# XMICRO-LPA_V1_0.net
KiCad netlist of a schematic drawn in EAGLE
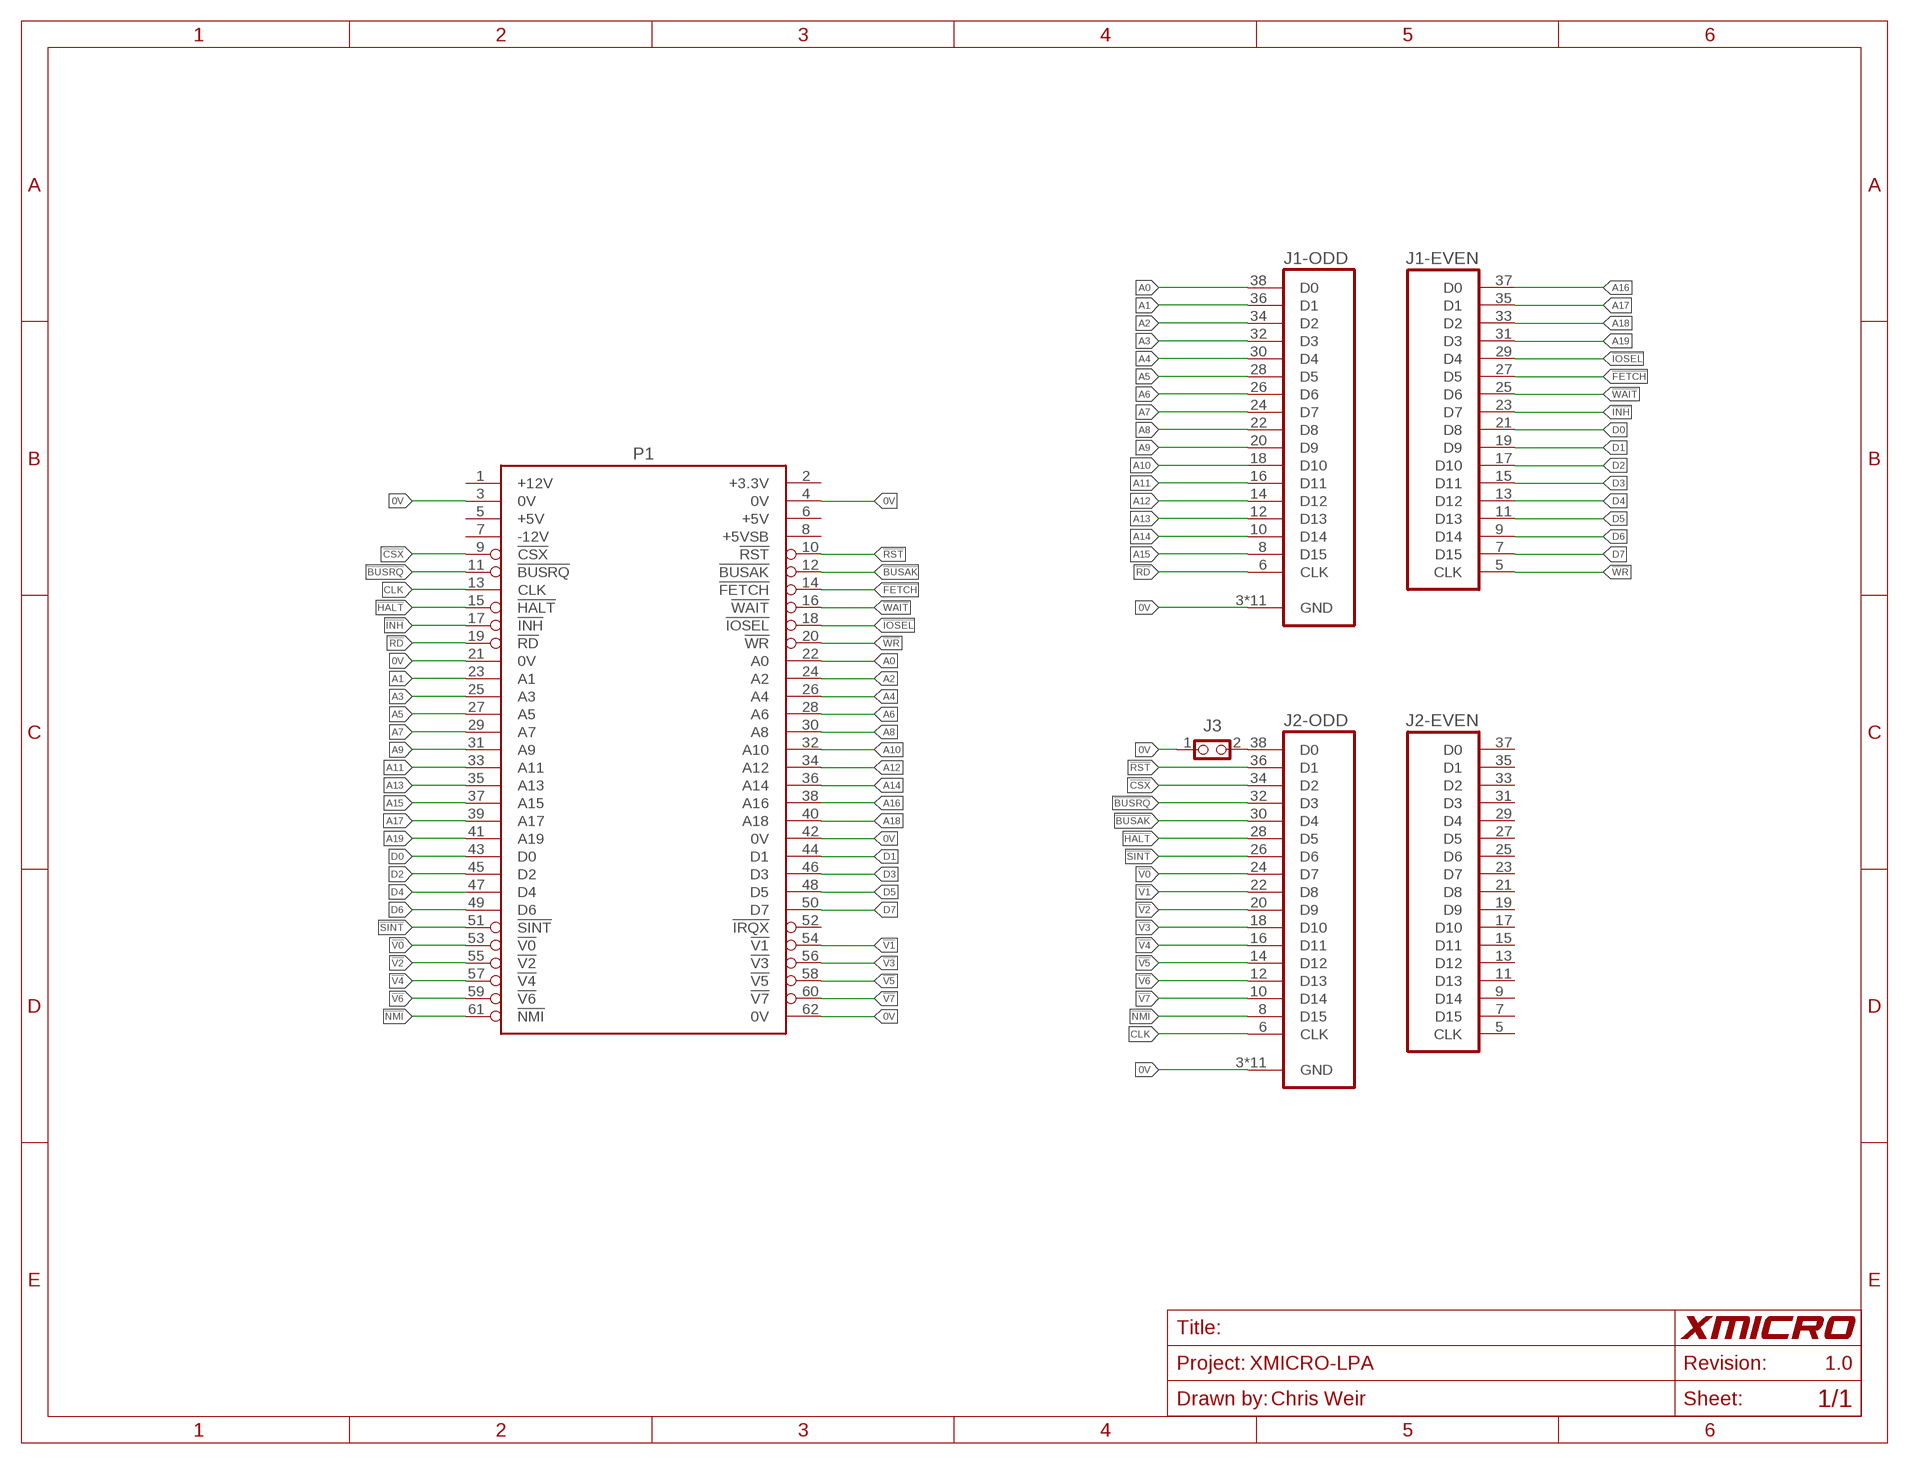
[diagram p0: schematic, sheet 1]

(export (version "E")
  (design (tool "Eeschema 10.0.6"))
  (components
    (comp (ref "J1")
      (value "LA-34MEB")
      (footprint "eagle-import:5767089-1B")
      (libsource (lib "eagle-import") (part "LA-34MEB"))
    )
    (comp (ref "J2")
      (value "LA-34MEB")
      (footprint "eagle-import:5767089-1B")
      (libsource (lib "eagle-import") (part "LA-34MEB"))
    )
    (comp (ref "J3")
      (value "1X2-THRU")
      (footprint "eagle-import:1X2")
      (libsource (lib "eagle-import") (part "1X2-THRU"))
    )
    (comp (ref "P1")
      (value "XMICRO-BUS-PHYSICAL-M")
      (footprint "eagle-import:EDGE62M")
      (libsource (lib "eagle-import") (part "XMICRO-BUS-PHYSICAL-M"))
    )
  )
  (nets
    (net (code "1") (name "/~{BUSAK}") (class "Default")
      (node (ref "J2") (pin "30") (pinfunction "D4_30") (pintype "passive"))
      (node (ref "P1") (pin "12") (pinfunction "~{BUSAK}_12") (pintype "bidirectional"))
    )
    (net (code "2") (name "/~{BUSRQ}") (class "Default")
      (node (ref "J2") (pin "32") (pinfunction "D3_32") (pintype "passive"))
      (node (ref "P1") (pin "11") (pinfunction "~{BUSRQ}_11") (pintype "bidirectional"))
    )
    (net (code "3") (name "/~{CSX}") (class "Default")
      (node (ref "J2") (pin "34") (pinfunction "D2_34") (pintype "passive"))
      (node (ref "P1") (pin "9") (pinfunction "~{CSX}_9") (pintype "bidirectional"))
    )
    (net (code "4") (name "/~{FETCH}") (class "Default")
      (node (ref "J1") (pin "27") (pinfunction "D5_27") (pintype "passive"))
      (node (ref "P1") (pin "14") (pinfunction "~{FETCH}_14") (pintype "bidirectional"))
    )
    (net (code "5") (name "/~{HALT}") (class "Default")
      (node (ref "J2") (pin "28") (pinfunction "D5_28") (pintype "passive"))
      (node (ref "P1") (pin "15") (pinfunction "~{HALT}_15") (pintype "bidirectional"))
    )
    (net (code "6") (name "/~{INH}") (class "Default")
      (node (ref "J1") (pin "23") (pinfunction "D7_23") (pintype "passive"))
      (node (ref "P1") (pin "17") (pinfunction "~{INH}_17") (pintype "bidirectional"))
    )
    (net (code "7") (name "/~{IOSEL}") (class "Default")
      (node (ref "J1") (pin "29") (pinfunction "D4_29") (pintype "passive"))
      (node (ref "P1") (pin "18") (pinfunction "~{IOSEL}_18") (pintype "bidirectional"))
    )
    (net (code "8") (name "/~{NMI}") (class "Default")
      (node (ref "J2") (pin "8") (pinfunction "D15_8") (pintype "passive"))
      (node (ref "P1") (pin "61") (pinfunction "~{NMI}_61") (pintype "bidirectional"))
    )
    (net (code "9") (name "/~{RD}") (class "Default")
      (node (ref "J1") (pin "6") (pinfunction "CLK_6") (pintype "passive"))
      (node (ref "P1") (pin "19") (pinfunction "~{RD}_19") (pintype "bidirectional"))
    )
    (net (code "10") (name "/~{RST}") (class "Default")
      (node (ref "J2") (pin "36") (pinfunction "D1_36") (pintype "passive"))
      (node (ref "P1") (pin "10") (pinfunction "~{RST}_10") (pintype "bidirectional"))
    )
    (net (code "11") (name "/~{SINT}") (class "Default")
      (node (ref "J2") (pin "26") (pinfunction "D6_26") (pintype "passive"))
      (node (ref "P1") (pin "51") (pinfunction "~{SINT}_51") (pintype "bidirectional"))
    )
    (net (code "12") (name "/~{V0}") (class "Default")
      (node (ref "J2") (pin "24") (pinfunction "D7_24") (pintype "passive"))
      (node (ref "P1") (pin "53") (pinfunction "~{V0}_53") (pintype "bidirectional"))
    )
    (net (code "13") (name "/~{V1}") (class "Default")
      (node (ref "J2") (pin "22") (pinfunction "D8_22") (pintype "passive"))
      (node (ref "P1") (pin "54") (pinfunction "~{V1}_54") (pintype "bidirectional"))
    )
    (net (code "14") (name "/~{V2}") (class "Default")
      (node (ref "J2") (pin "20") (pinfunction "D9_20") (pintype "passive"))
      (node (ref "P1") (pin "55") (pinfunction "~{V2}_55") (pintype "bidirectional"))
    )
    (net (code "15") (name "/~{V3}") (class "Default")
      (node (ref "J2") (pin "18") (pinfunction "D10_18") (pintype "passive"))
      (node (ref "P1") (pin "56") (pinfunction "~{V3}_56") (pintype "bidirectional"))
    )
    (net (code "16") (name "/~{V4}") (class "Default")
      (node (ref "J2") (pin "16") (pinfunction "D11_16") (pintype "passive"))
      (node (ref "P1") (pin "57") (pinfunction "~{V4}_57") (pintype "bidirectional"))
    )
    (net (code "17") (name "/~{V5}") (class "Default")
      (node (ref "J2") (pin "14") (pinfunction "D12_14") (pintype "passive"))
      (node (ref "P1") (pin "58") (pinfunction "~{V5}_58") (pintype "bidirectional"))
    )
    (net (code "18") (name "/~{V6}") (class "Default")
      (node (ref "J2") (pin "12") (pinfunction "D13_12") (pintype "passive"))
      (node (ref "P1") (pin "59") (pinfunction "~{V6}_59") (pintype "bidirectional"))
    )
    (net (code "19") (name "/~{V7}") (class "Default")
      (node (ref "J2") (pin "10") (pinfunction "D14_10") (pintype "passive"))
      (node (ref "P1") (pin "60") (pinfunction "~{V7}_60") (pintype "bidirectional"))
    )
    (net (code "20") (name "/~{WAIT}") (class "Default")
      (node (ref "J1") (pin "25") (pinfunction "D6_25") (pintype "passive"))
      (node (ref "P1") (pin "16") (pinfunction "~{WAIT}_16") (pintype "bidirectional"))
    )
    (net (code "21") (name "/~{WR}") (class "Default")
      (node (ref "J1") (pin "5") (pinfunction "CLK_5") (pintype "passive"))
      (node (ref "P1") (pin "20") (pinfunction "~{WR}_20") (pintype "bidirectional"))
    )
    (net (code "22") (name "0V") (class "Default")
      (node (ref "J1") (pin "3") (pinfunction "GND_3") (pintype "passive"))
      (node (ref "J1") (pin "G1") (pinfunction "GND_G1") (pintype "passive"))
      (node (ref "J1") (pin "G10") (pinfunction "GND_G10") (pintype "passive"))
      (node (ref "J1") (pin "G2") (pinfunction "GND_G2") (pintype "passive"))
      (node (ref "J1") (pin "G3") (pinfunction "GND_G3") (pintype "passive"))
      (node (ref "J1") (pin "G4") (pinfunction "GND_G4") (pintype "passive"))
      (node (ref "J1") (pin "G5") (pinfunction "GND_G5") (pintype "passive"))
      (node (ref "J1") (pin "G6") (pinfunction "GND_G6") (pintype "passive"))
      (node (ref "J1") (pin "G7") (pinfunction "GND_G7") (pintype "passive"))
      (node (ref "J1") (pin "G8") (pinfunction "GND_G8") (pintype "passive"))
      (node (ref "J1") (pin "G9") (pinfunction "GND_G9") (pintype "passive"))
      (node (ref "J2") (pin "3") (pinfunction "GND_3") (pintype "passive"))
      (node (ref "J2") (pin "G1") (pinfunction "GND_G1") (pintype "passive"))
      (node (ref "J2") (pin "G10") (pinfunction "GND_G10") (pintype "passive"))
      (node (ref "J2") (pin "G2") (pinfunction "GND_G2") (pintype "passive"))
      (node (ref "J2") (pin "G3") (pinfunction "GND_G3") (pintype "passive"))
      (node (ref "J2") (pin "G4") (pinfunction "GND_G4") (pintype "passive"))
      (node (ref "J2") (pin "G5") (pinfunction "GND_G5") (pintype "passive"))
      (node (ref "J2") (pin "G6") (pinfunction "GND_G6") (pintype "passive"))
      (node (ref "J2") (pin "G7") (pinfunction "GND_G7") (pintype "passive"))
      (node (ref "J2") (pin "G8") (pinfunction "GND_G8") (pintype "passive"))
      (node (ref "J2") (pin "G9") (pinfunction "GND_G9") (pintype "passive"))
      (node (ref "J3") (pin "1") (pinfunction "1_1") (pintype "passive"))
      (node (ref "P1") (pin "21") (pinfunction "0V_21") (pintype "bidirectional"))
      (node (ref "P1") (pin "3") (pinfunction "0V_3") (pintype "bidirectional"))
      (node (ref "P1") (pin "4") (pinfunction "0V_4") (pintype "bidirectional"))
      (node (ref "P1") (pin "42") (pinfunction "0V_42") (pintype "bidirectional"))
      (node (ref "P1") (pin "62") (pinfunction "0V_62") (pintype "bidirectional"))
    )
    (net (code "23") (name "A0") (class "Default")
      (node (ref "J1") (pin "38") (pinfunction "D0_38") (pintype "passive"))
      (node (ref "P1") (pin "22") (pinfunction "A0_22") (pintype "bidirectional"))
    )
    (net (code "24") (name "A1") (class "Default")
      (node (ref "J1") (pin "36") (pinfunction "D1_36") (pintype "passive"))
      (node (ref "P1") (pin "23") (pinfunction "A1_23") (pintype "bidirectional"))
    )
    (net (code "25") (name "A2") (class "Default")
      (node (ref "J1") (pin "34") (pinfunction "D2_34") (pintype "passive"))
      (node (ref "P1") (pin "24") (pinfunction "A2_24") (pintype "bidirectional"))
    )
    (net (code "26") (name "A3") (class "Default")
      (node (ref "J1") (pin "32") (pinfunction "D3_32") (pintype "passive"))
      (node (ref "P1") (pin "25") (pinfunction "A3_25") (pintype "bidirectional"))
    )
    (net (code "27") (name "A4") (class "Default")
      (node (ref "J1") (pin "30") (pinfunction "D4_30") (pintype "passive"))
      (node (ref "P1") (pin "26") (pinfunction "A4_26") (pintype "bidirectional"))
    )
    (net (code "28") (name "A5") (class "Default")
      (node (ref "J1") (pin "28") (pinfunction "D5_28") (pintype "passive"))
      (node (ref "P1") (pin "27") (pinfunction "A5_27") (pintype "bidirectional"))
    )
    (net (code "29") (name "A6") (class "Default")
      (node (ref "J1") (pin "26") (pinfunction "D6_26") (pintype "passive"))
      (node (ref "P1") (pin "28") (pinfunction "A6_28") (pintype "bidirectional"))
    )
    (net (code "30") (name "A7") (class "Default")
      (node (ref "J1") (pin "24") (pinfunction "D7_24") (pintype "passive"))
      (node (ref "P1") (pin "29") (pinfunction "A7_29") (pintype "bidirectional"))
    )
    (net (code "31") (name "A8") (class "Default")
      (node (ref "J1") (pin "22") (pinfunction "D8_22") (pintype "passive"))
      (node (ref "P1") (pin "30") (pinfunction "A8_30") (pintype "bidirectional"))
    )
    (net (code "32") (name "A9") (class "Default")
      (node (ref "J1") (pin "20") (pinfunction "D9_20") (pintype "passive"))
      (node (ref "P1") (pin "31") (pinfunction "A9_31") (pintype "bidirectional"))
    )
    (net (code "33") (name "A10") (class "Default")
      (node (ref "J1") (pin "18") (pinfunction "D10_18") (pintype "passive"))
      (node (ref "P1") (pin "32") (pinfunction "A10_32") (pintype "bidirectional"))
    )
    (net (code "34") (name "A11") (class "Default")
      (node (ref "J1") (pin "16") (pinfunction "D11_16") (pintype "passive"))
      (node (ref "P1") (pin "33") (pinfunction "A11_33") (pintype "bidirectional"))
    )
    (net (code "35") (name "A12") (class "Default")
      (node (ref "J1") (pin "14") (pinfunction "D12_14") (pintype "passive"))
      (node (ref "P1") (pin "34") (pinfunction "A12_34") (pintype "bidirectional"))
    )
    (net (code "36") (name "A13") (class "Default")
      (node (ref "J1") (pin "12") (pinfunction "D13_12") (pintype "passive"))
      (node (ref "P1") (pin "35") (pinfunction "A13_35") (pintype "bidirectional"))
    )
    (net (code "37") (name "A14") (class "Default")
      (node (ref "J1") (pin "10") (pinfunction "D14_10") (pintype "passive"))
      (node (ref "P1") (pin "36") (pinfunction "A14_36") (pintype "bidirectional"))
    )
    (net (code "38") (name "A15") (class "Default")
      (node (ref "J1") (pin "8") (pinfunction "D15_8") (pintype "passive"))
      (node (ref "P1") (pin "37") (pinfunction "A15_37") (pintype "bidirectional"))
    )
    (net (code "39") (name "A16") (class "Default")
      (node (ref "J1") (pin "37") (pinfunction "D0_37") (pintype "passive"))
      (node (ref "P1") (pin "38") (pinfunction "A16_38") (pintype "bidirectional"))
    )
    (net (code "40") (name "A17") (class "Default")
      (node (ref "J1") (pin "35") (pinfunction "D1_35") (pintype "passive"))
      (node (ref "P1") (pin "39") (pinfunction "A17_39") (pintype "bidirectional"))
    )
    (net (code "41") (name "A18") (class "Default")
      (node (ref "J1") (pin "33") (pinfunction "D2_33") (pintype "passive"))
      (node (ref "P1") (pin "40") (pinfunction "A18_40") (pintype "bidirectional"))
    )
    (net (code "42") (name "A19") (class "Default")
      (node (ref "J1") (pin "31") (pinfunction "D3_31") (pintype "passive"))
      (node (ref "P1") (pin "41") (pinfunction "A19_41") (pintype "bidirectional"))
    )
    (net (code "43") (name "CLK") (class "Default")
      (node (ref "J2") (pin "6") (pinfunction "CLK_6") (pintype "passive"))
      (node (ref "P1") (pin "13") (pinfunction "CLK_13") (pintype "bidirectional"))
    )
    (net (code "44") (name "D0") (class "Default")
      (node (ref "J1") (pin "21") (pinfunction "D8_21") (pintype "passive"))
      (node (ref "P1") (pin "43") (pinfunction "D0_43") (pintype "bidirectional"))
    )
    (net (code "45") (name "D1") (class "Default")
      (node (ref "J1") (pin "19") (pinfunction "D9_19") (pintype "passive"))
      (node (ref "P1") (pin "44") (pinfunction "D1_44") (pintype "bidirectional"))
    )
    (net (code "46") (name "D2") (class "Default")
      (node (ref "J1") (pin "17") (pinfunction "D10_17") (pintype "passive"))
      (node (ref "P1") (pin "45") (pinfunction "D2_45") (pintype "bidirectional"))
    )
    (net (code "47") (name "D3") (class "Default")
      (node (ref "J1") (pin "15") (pinfunction "D11_15") (pintype "passive"))
      (node (ref "P1") (pin "46") (pinfunction "D3_46") (pintype "bidirectional"))
    )
    (net (code "48") (name "D4") (class "Default")
      (node (ref "J1") (pin "13") (pinfunction "D12_13") (pintype "passive"))
      (node (ref "P1") (pin "47") (pinfunction "D4_47") (pintype "bidirectional"))
    )
    (net (code "49") (name "D5") (class "Default")
      (node (ref "J1") (pin "11") (pinfunction "D13_11") (pintype "passive"))
      (node (ref "P1") (pin "48") (pinfunction "D5_48") (pintype "bidirectional"))
    )
    (net (code "50") (name "D6") (class "Default")
      (node (ref "J1") (pin "9") (pinfunction "D14_9") (pintype "passive"))
      (node (ref "P1") (pin "49") (pinfunction "D6_49") (pintype "bidirectional"))
    )
    (net (code "51") (name "D7") (class "Default")
      (node (ref "J1") (pin "7") (pinfunction "D15_7") (pintype "passive"))
      (node (ref "P1") (pin "50") (pinfunction "D7_50") (pintype "bidirectional"))
    )
    (net (code "52") (name "Net-(J2B-D0)") (class "Default")
      (node (ref "J2") (pin "38") (pinfunction "D0_38") (pintype "passive"))
      (node (ref "J3") (pin "2") (pinfunction "2_2") (pintype "passive"))
    )
    (net (code "53") (name "unconnected-(J2A-CLK-Pad5)") (class "Default")
      (node (ref "J2") (pin "5") (pinfunction "CLK_5") (pintype "passive"))
    )
    (net (code "54") (name "unconnected-(J2A-D0-Pad37)") (class "Default")
      (node (ref "J2") (pin "37") (pinfunction "D0_37") (pintype "passive"))
    )
    (net (code "55") (name "unconnected-(J2A-D1-Pad35)") (class "Default")
      (node (ref "J2") (pin "35") (pinfunction "D1_35") (pintype "passive"))
    )
    (net (code "56") (name "unconnected-(J2A-D2-Pad33)") (class "Default")
      (node (ref "J2") (pin "33") (pinfunction "D2_33") (pintype "passive"))
    )
    (net (code "57") (name "unconnected-(J2A-D3-Pad31)") (class "Default")
      (node (ref "J2") (pin "31") (pinfunction "D3_31") (pintype "passive"))
    )
    (net (code "58") (name "unconnected-(J2A-D4-Pad29)") (class "Default")
      (node (ref "J2") (pin "29") (pinfunction "D4_29") (pintype "passive"))
    )
    (net (code "59") (name "unconnected-(J2A-D5-Pad27)") (class "Default")
      (node (ref "J2") (pin "27") (pinfunction "D5_27") (pintype "passive"))
    )
    (net (code "60") (name "unconnected-(J2A-D6-Pad25)") (class "Default")
      (node (ref "J2") (pin "25") (pinfunction "D6_25") (pintype "passive"))
    )
    (net (code "61") (name "unconnected-(J2A-D7-Pad23)") (class "Default")
      (node (ref "J2") (pin "23") (pinfunction "D7_23") (pintype "passive"))
    )
    (net (code "62") (name "unconnected-(J2A-D8-Pad21)") (class "Default")
      (node (ref "J2") (pin "21") (pinfunction "D8_21") (pintype "passive"))
    )
    (net (code "63") (name "unconnected-(J2A-D9-Pad19)") (class "Default")
      (node (ref "J2") (pin "19") (pinfunction "D9_19") (pintype "passive"))
    )
    (net (code "64") (name "unconnected-(J2A-D10-Pad17)") (class "Default")
      (node (ref "J2") (pin "17") (pinfunction "D10_17") (pintype "passive"))
    )
    (net (code "65") (name "unconnected-(J2A-D11-Pad15)") (class "Default")
      (node (ref "J2") (pin "15") (pinfunction "D11_15") (pintype "passive"))
    )
    (net (code "66") (name "unconnected-(J2A-D12-Pad13)") (class "Default")
      (node (ref "J2") (pin "13") (pinfunction "D12_13") (pintype "passive"))
    )
    (net (code "67") (name "unconnected-(J2A-D13-Pad11)") (class "Default")
      (node (ref "J2") (pin "11") (pinfunction "D13_11") (pintype "passive"))
    )
    (net (code "68") (name "unconnected-(J2A-D14-Pad9)") (class "Default")
      (node (ref "J2") (pin "9") (pinfunction "D14_9") (pintype "passive"))
    )
    (net (code "69") (name "unconnected-(J2A-D15-Pad7)") (class "Default")
      (node (ref "J2") (pin "7") (pinfunction "D15_7") (pintype "passive"))
    )
    (net (code "70") (name "unconnected-(P1-+3.3V-Pad2)") (class "Default")
      (node (ref "P1") (pin "2") (pinfunction "+3.3V_2") (pintype "bidirectional"))
    )
    (net (code "71") (name "unconnected-(P1-+5V-Pad5)") (class "Default")
      (node (ref "P1") (pin "5") (pinfunction "+5V_5") (pintype "bidirectional"))
    )
    (net (code "72") (name "unconnected-(P1-+5V-Pad6)") (class "Default")
      (node (ref "P1") (pin "6") (pinfunction "+5V_6") (pintype "bidirectional"))
    )
    (net (code "73") (name "unconnected-(P1-+5VSB-Pad8)") (class "Default")
      (node (ref "P1") (pin "8") (pinfunction "+5VSB_8") (pintype "bidirectional"))
    )
    (net (code "74") (name "unconnected-(P1-+12V-Pad1)") (class "Default")
      (node (ref "P1") (pin "1") (pinfunction "+12V_1") (pintype "bidirectional"))
    )
    (net (code "75") (name "unconnected-(P1--12V-Pad7)") (class "Default")
      (node (ref "P1") (pin "7") (pinfunction "-12V_7") (pintype "bidirectional"))
    )
    (net (code "76") (name "unconnected-(P1-~{IRQX}-Pad52)") (class "Default")
      (node (ref "P1") (pin "52") (pinfunction "~{IRQX}_52") (pintype "bidirectional"))
    )
  )
)
